# Audio_Connectors.net
KiCad netlist of a schematic drawn in Altium Designer
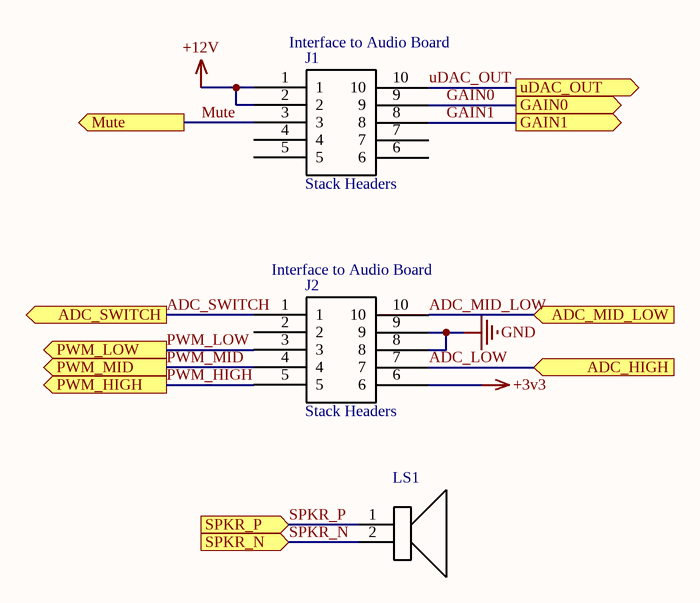
[diagram p0: Audio_Connectors.SchDoc]

(export (version "E")
  (design (tool "Eeschema 10.0.6"))
  (components
    (comp (ref "J1")
      (value "Stack Headers")
      (footprint "SSW-105")
      (libsource (lib "SpeakEasy") (part "Stack Headers"))
    )
    (comp (ref "J2")
      (value "Stack Headers")
      (footprint "SSW-105")
      (libsource (lib "SpeakEasy") (part "Stack Headers"))
    )
    (comp (ref "LS1")
      (value "Made for use with 20AWG")
      (footprint "Speaker")
      (libsource (lib "SpeakEasy") (part "Speaker_Footprint"))
    )
  )
  (nets
    (net (code "1") (name "+3v3") (class "Default")
      (node (ref "J2") (pin "6") (pinfunction "6_6") (pintype "passive"))
    )
    (net (code "2") (name "+12V") (class "Default")
      (node (ref "J1") (pin "1") (pinfunction "1_1") (pintype "passive"))
      (node (ref "J1") (pin "2") (pinfunction "2_2") (pintype "passive"))
    )
    (net (code "3") (name "/ADC_LOW") (class "Default")
      (node (ref "J2") (pin "7") (pinfunction "7_7") (pintype "passive"))
    )
    (net (code "4") (name "/ADC_MID_LOW") (class "Default")
      (node (ref "J2") (pin "10") (pinfunction "10_10") (pintype "passive"))
    )
    (net (code "5") (name "/ADC_SWITCH") (class "Default")
      (node (ref "J2") (pin "1") (pinfunction "1_1") (pintype "passive"))
    )
    (net (code "6") (name "/GAIN0") (class "Default")
      (node (ref "J1") (pin "9") (pinfunction "9_9") (pintype "passive"))
    )
    (net (code "7") (name "/GAIN1") (class "Default")
      (node (ref "J1") (pin "8") (pinfunction "8_8") (pintype "passive"))
    )
    (net (code "8") (name "/Mute") (class "Default")
      (node (ref "J1") (pin "3") (pinfunction "3_3") (pintype "passive"))
    )
    (net (code "9") (name "/PWM_HIGH") (class "Default")
      (node (ref "J2") (pin "5") (pinfunction "5_5") (pintype "passive"))
    )
    (net (code "10") (name "/PWM_LOW") (class "Default")
      (node (ref "J2") (pin "3") (pinfunction "3_3") (pintype "passive"))
    )
    (net (code "11") (name "/PWM_MID") (class "Default")
      (node (ref "J2") (pin "4") (pinfunction "4_4") (pintype "passive"))
    )
    (net (code "12") (name "/SPKR_N") (class "Default")
      (node (ref "LS1") (pin "2") (pinfunction "4_2") (pintype "passive"))
    )
    (net (code "13") (name "/SPKR_P") (class "Default")
      (node (ref "LS1") (pin "1") (pinfunction "3_1") (pintype "passive"))
    )
    (net (code "14") (name "/uDAC_OUT") (class "Default")
      (node (ref "J1") (pin "10") (pinfunction "10_10") (pintype "passive"))
    )
    (net (code "15") (name "GND") (class "Default")
      (node (ref "J2") (pin "8") (pinfunction "8_8") (pintype "passive"))
      (node (ref "J2") (pin "9") (pinfunction "9_9") (pintype "passive"))
    )
    (net (code "16") (name "unconnected-(J1-Pad4)") (class "Default")
      (node (ref "J1") (pin "4") (pinfunction "4_4") (pintype "passive"))
    )
    (net (code "17") (name "unconnected-(J1-Pad5)") (class "Default")
      (node (ref "J1") (pin "5") (pinfunction "5_5") (pintype "passive"))
    )
    (net (code "18") (name "unconnected-(J1-Pad6)") (class "Default")
      (node (ref "J1") (pin "6") (pinfunction "6_6") (pintype "passive"))
    )
    (net (code "19") (name "unconnected-(J1-Pad7)") (class "Default")
      (node (ref "J1") (pin "7") (pinfunction "7_7") (pintype "passive"))
    )
    (net (code "20") (name "unconnected-(J2-Pad2)") (class "Default")
      (node (ref "J2") (pin "2") (pinfunction "2_2") (pintype "passive"))
    )
  )
)
